# Schematic.net
KiCad netlist of a schematic drawn in Altium Designer
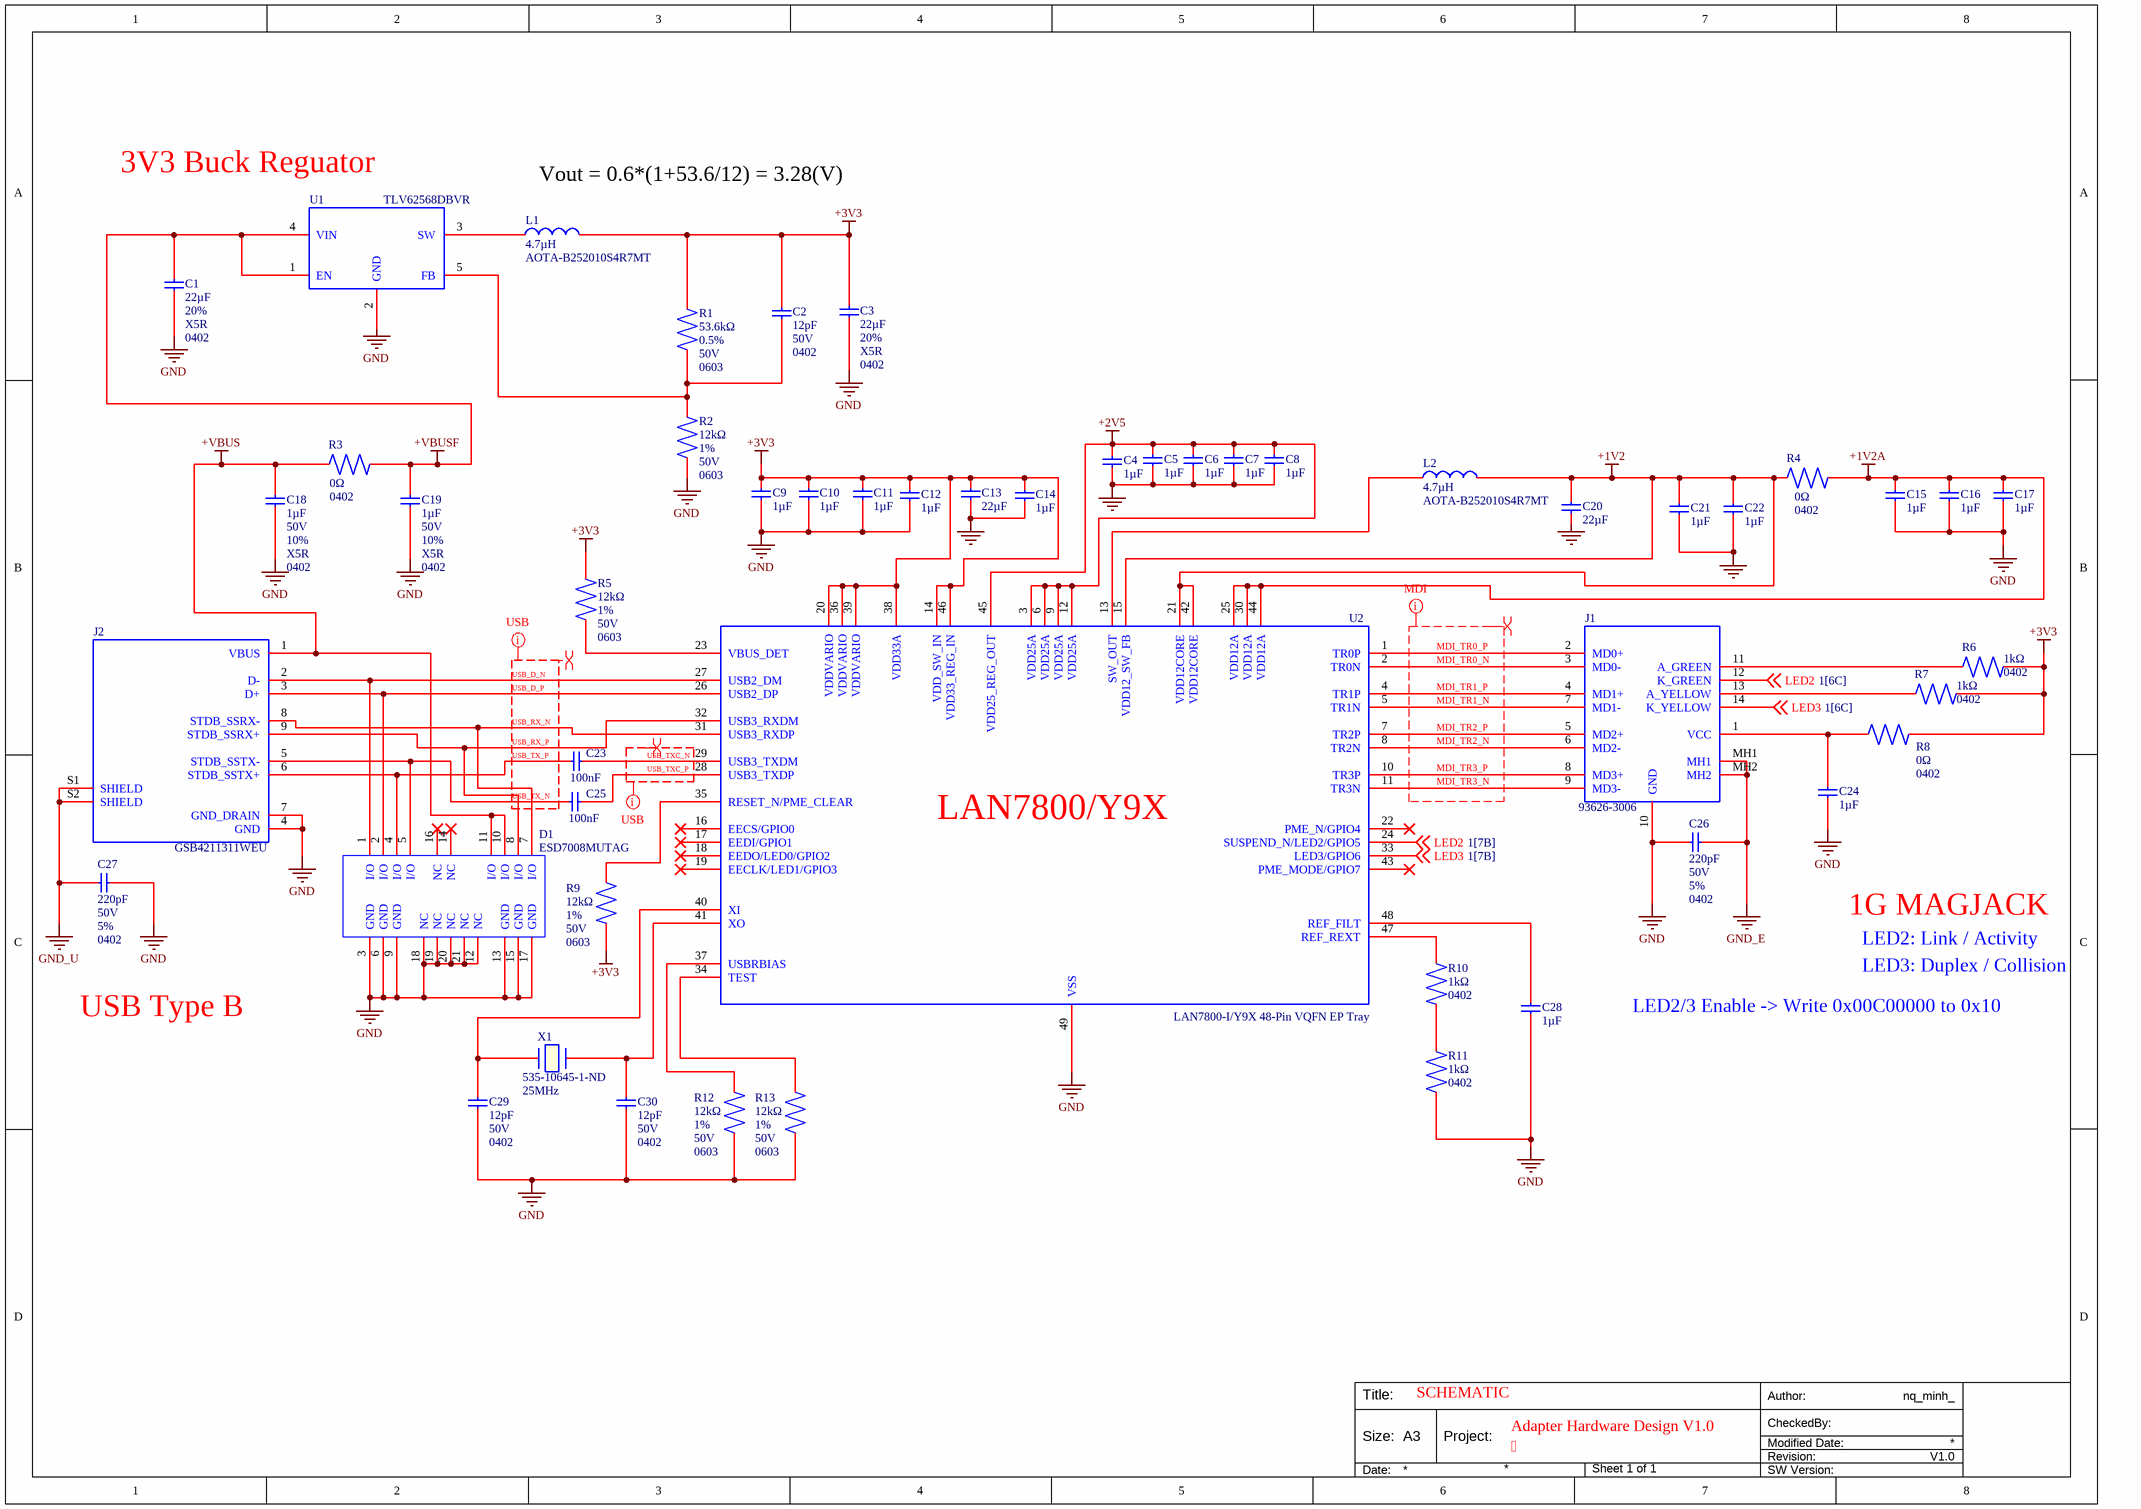
[diagram p0: Schematic.SchDoc]

(export (version "E")
  (design (tool "Eeschema 10.0.6"))
  (components
    (comp (ref "C1")
      (value "22µF")
      (footprint "C0402")
      (description "6.3V 22uF X5R ±20% 0402 Multilayer Ceramic Capacitors MLCC - SMD/SMT ROHS")
      (fields
        (field (name "MANUFACTURER") "Murata")
        (field (name "MANUFACTURER PART NUMBER") "GRM155R60J226ME11D")
        (field (name "TOLERANCE") "20%")
        (field (name "DIELECTRIC") "X5R")
        (field (name "CASE/PACKAGE") "0402")
      )
      (libsource (lib "Schlib") (part "C0402_MLCC_22uF_X5R_6.3V"))
    )
    (comp (ref "C2")
      (value "12pF")
      (footprint "C0402")
      (description "50V 12pF C0G ±1% 0402 Multilayer Ceramic Capacitors MLCC - SMD/SMT ROHS")
      (fields
        (field (name "MANUFACTURER") "Murata")
        (field (name "MANUFACTURER PART NUMBER") "GCM1555C1H120FA16D")
        (field (name "VOLTAGE RATING") "50V")
        (field (name "CASE/PACKAGE") "0402")
      )
      (libsource (lib "Schlib") (part "C0402_MLCC_12pF_c0G_50V"))
    )
    (comp (ref "C3")
      (value "22µF")
      (footprint "C0402")
      (description "6.3V 22uF X5R ±20% 0402 Multilayer Ceramic Capacitors MLCC - SMD/SMT ROHS")
      (fields
        (field (name "MANUFACTURER") "Murata")
        (field (name "MANUFACTURER PART NUMBER") "GRM155R60J226ME11D")
        (field (name "TOLERANCE") "20%")
        (field (name "DIELECTRIC") "X5R")
        (field (name "CASE/PACKAGE") "0402")
      )
      (libsource (lib "Schlib") (part "C0402_MLCC_22uF_X5R_6.3V"))
    )
    (comp (ref "C4")
      (value "1µF")
      (footprint "C0402")
      (description "Ceramic Capacitor, Multilayer, Ceramic, 50V, 10% +Tol, 10% -Tol, X5R, 1uF, Surface Mount, 0402")
      (fields
        (field (name "MANUFACTURER") "Murata")
        (field (name "MANUFACTURER PART NUMBER") "GRM155R61H105KE05D")
      )
      (libsource (lib "Schlib") (part "C0402_MLCC_1uF_X5R_50V"))
    )
    (comp (ref "C5")
      (value "1µF")
      (footprint "C0402")
      (description "Ceramic Capacitor, Multilayer, Ceramic, 50V, 10% +Tol, 10% -Tol, X5R, 1uF, Surface Mount, 0402")
      (fields
        (field (name "MANUFACTURER") "Murata")
        (field (name "MANUFACTURER PART NUMBER") "GRM155R61H105KE05D")
      )
      (libsource (lib "Schlib") (part "C0402_MLCC_1uF_X5R_50V"))
    )
    (comp (ref "C6")
      (value "1µF")
      (footprint "C0402")
      (description "Ceramic Capacitor, Multilayer, Ceramic, 50V, 10% +Tol, 10% -Tol, X5R, 1uF, Surface Mount, 0402")
      (fields
        (field (name "MANUFACTURER") "Murata")
        (field (name "MANUFACTURER PART NUMBER") "GRM155R61H105KE05D")
      )
      (libsource (lib "Schlib") (part "C0402_MLCC_1uF_X5R_50V"))
    )
    (comp (ref "C7")
      (value "1µF")
      (footprint "C0402")
      (description "Ceramic Capacitor, Multilayer, Ceramic, 50V, 10% +Tol, 10% -Tol, X5R, 1uF, Surface Mount, 0402")
      (fields
        (field (name "MANUFACTURER") "Murata")
        (field (name "MANUFACTURER PART NUMBER") "GRM155R61H105KE05D")
      )
      (libsource (lib "Schlib") (part "C0402_MLCC_1uF_X5R_50V"))
    )
    (comp (ref "C8")
      (value "1µF")
      (footprint "C0402")
      (description "Ceramic Capacitor, Multilayer, Ceramic, 50V, 10% +Tol, 10% -Tol, X5R, 1uF, Surface Mount, 0402")
      (fields
        (field (name "MANUFACTURER") "Murata")
        (field (name "MANUFACTURER PART NUMBER") "GRM155R61H105KE05D")
      )
      (libsource (lib "Schlib") (part "C0402_MLCC_1uF_X5R_50V"))
    )
    (comp (ref "C9")
      (value "1µF")
      (footprint "C0402")
      (description "Ceramic Capacitor, Multilayer, Ceramic, 50V, 10% +Tol, 10% -Tol, X5R, 1uF, Surface Mount, 0402")
      (fields
        (field (name "MANUFACTURER") "Murata")
        (field (name "MANUFACTURER PART NUMBER") "GRM155R61H105KE05D")
      )
      (libsource (lib "Schlib") (part "C0402_MLCC_1uF_X5R_50V"))
    )
    (comp (ref "C10")
      (value "1µF")
      (footprint "C0402")
      (description "Ceramic Capacitor, Multilayer, Ceramic, 50V, 10% +Tol, 10% -Tol, X5R, 1uF, Surface Mount, 0402")
      (fields
        (field (name "MANUFACTURER") "Murata")
        (field (name "MANUFACTURER PART NUMBER") "GRM155R61H105KE05D")
      )
      (libsource (lib "Schlib") (part "C0402_MLCC_1uF_X5R_50V"))
    )
    (comp (ref "C11")
      (value "1µF")
      (footprint "C0402")
      (description "Ceramic Capacitor, Multilayer, Ceramic, 50V, 10% +Tol, 10% -Tol, X5R, 1uF, Surface Mount, 0402")
      (fields
        (field (name "MANUFACTURER") "Murata")
        (field (name "MANUFACTURER PART NUMBER") "GRM155R61H105KE05D")
      )
      (libsource (lib "Schlib") (part "C0402_MLCC_1uF_X5R_50V"))
    )
    (comp (ref "C12")
      (value "1µF")
      (footprint "C0402")
      (description "Ceramic Capacitor, Multilayer, Ceramic, 50V, 10% +Tol, 10% -Tol, X5R, 1uF, Surface Mount, 0402")
      (fields
        (field (name "MANUFACTURER") "Murata")
        (field (name "MANUFACTURER PART NUMBER") "GRM155R61H105KE05D")
      )
      (libsource (lib "Schlib") (part "C0402_MLCC_1uF_X5R_50V"))
    )
    (comp (ref "C13")
      (value "22µF")
      (footprint "C0402")
      (description "6.3V 22uF X5R ±20% 0402 Multilayer Ceramic Capacitors MLCC - SMD/SMT ROHS")
      (fields
        (field (name "MANUFACTURER") "Murata")
        (field (name "MANUFACTURER PART NUMBER") "GRM155R60J226ME11D")
      )
      (libsource (lib "Schlib") (part "C0402_MLCC_22uF_X5R_6.3V"))
    )
    (comp (ref "C14")
      (value "1µF")
      (footprint "C0402")
      (description "Ceramic Capacitor, Multilayer, Ceramic, 50V, 10% +Tol, 10% -Tol, X5R, 1uF, Surface Mount, 0402")
      (fields
        (field (name "MANUFACTURER") "Murata")
        (field (name "MANUFACTURER PART NUMBER") "GRM155R61H105KE05D")
      )
      (libsource (lib "Schlib") (part "C0402_MLCC_1uF_X5R_50V"))
    )
    (comp (ref "C15")
      (value "1µF")
      (footprint "C0402")
      (description "Ceramic Capacitor, Multilayer, Ceramic, 50V, 10% +Tol, 10% -Tol, X5R, 1uF, Surface Mount, 0402")
      (fields
        (field (name "MANUFACTURER") "Murata")
        (field (name "MANUFACTURER PART NUMBER") "GRM155R61H105KE05D")
      )
      (libsource (lib "Schlib") (part "C0402_MLCC_1uF_X5R_50V"))
    )
    (comp (ref "C16")
      (value "1µF")
      (footprint "C0402")
      (description "Ceramic Capacitor, Multilayer, Ceramic, 50V, 10% +Tol, 10% -Tol, X5R, 1uF, Surface Mount, 0402")
      (fields
        (field (name "MANUFACTURER") "Murata")
        (field (name "MANUFACTURER PART NUMBER") "GRM155R61H105KE05D")
      )
      (libsource (lib "Schlib") (part "C0402_MLCC_1uF_X5R_50V"))
    )
    (comp (ref "C17")
      (value "1µF")
      (footprint "C0402")
      (description "Ceramic Capacitor, Multilayer, Ceramic, 50V, 10% +Tol, 10% -Tol, X5R, 1uF, Surface Mount, 0402")
      (fields
        (field (name "MANUFACTURER") "Murata")
        (field (name "MANUFACTURER PART NUMBER") "GRM155R61H105KE05D")
      )
      (libsource (lib "Schlib") (part "C0402_MLCC_1uF_X5R_50V"))
    )
    (comp (ref "C18")
      (value "1µF")
      (footprint "C0402")
      (description "Ceramic Capacitor, Multilayer, Ceramic, 50V, 10% +Tol, 10% -Tol, X5R, 1uF, Surface Mount, 0402")
      (fields
        (field (name "MANUFACTURER") "Murata")
        (field (name "MANUFACTURER PART NUMBER") "GRM155R61H105KE05D")
        (field (name "VOLTAGE RATING") "50V")
        (field (name "TOLERANCE") "10%")
        (field (name "DIELECTRIC") "X5R")
        (field (name "CASE/PACKAGE") "0402")
      )
      (libsource (lib "Schlib") (part "C0402_MLCC_1uF_X5R_50V"))
    )
    (comp (ref "C19")
      (value "1µF")
      (footprint "C0402")
      (description "Ceramic Capacitor, Multilayer, Ceramic, 50V, 10% +Tol, 10% -Tol, X5R, 1uF, Surface Mount, 0402")
      (fields
        (field (name "MANUFACTURER") "Murata")
        (field (name "MANUFACTURER PART NUMBER") "GRM155R61H105KE05D")
        (field (name "VOLTAGE RATING") "50V")
        (field (name "TOLERANCE") "10%")
        (field (name "DIELECTRIC") "X5R")
        (field (name "CASE/PACKAGE") "0402")
      )
      (libsource (lib "Schlib") (part "C0402_MLCC_1uF_X5R_50V"))
    )
    (comp (ref "C20")
      (value "22µF")
      (footprint "C0402")
      (description "6.3V 22uF X5R ±20% 0402 Multilayer Ceramic Capacitors MLCC - SMD/SMT ROHS")
      (fields
        (field (name "MANUFACTURER") "Murata")
        (field (name "MANUFACTURER PART NUMBER") "GRM155R60J226ME11D")
      )
      (libsource (lib "Schlib") (part "C0402_MLCC_22uF_X5R_6.3V"))
    )
    (comp (ref "C21")
      (value "1µF")
      (footprint "C0402")
      (description "Ceramic Capacitor, Multilayer, Ceramic, 50V, 10% +Tol, 10% -Tol, X5R, 1uF, Surface Mount, 0402")
      (fields
        (field (name "MANUFACTURER") "Murata")
        (field (name "MANUFACTURER PART NUMBER") "GRM155R61H105KE05D")
      )
      (libsource (lib "Schlib") (part "C0402_MLCC_1uF_X5R_50V"))
    )
    (comp (ref "C22")
      (value "1µF")
      (footprint "C0402")
      (description "Ceramic Capacitor, Multilayer, Ceramic, 50V, 10% +Tol, 10% -Tol, X5R, 1uF, Surface Mount, 0402")
      (fields
        (field (name "MANUFACTURER") "Murata")
        (field (name "MANUFACTURER PART NUMBER") "GRM155R61H105KE05D")
      )
      (libsource (lib "Schlib") (part "C0402_MLCC_1uF_X5R_50V"))
    )
    (comp (ref "C23")
      (value "100nF")
      (footprint "C0402")
      (description "50V 100nF X7R ±10% 0402 Multilayer Ceramic Capacitors MLCC - SMD/SMT ROHS")
      (fields
        (field (name "MANUFACTURER") "Yageo Group")
        (field (name "MANUFACTURER PART NUMBER") "CC0402KRX7R9BB104")
      )
      (libsource (lib "Schlib") (part "C0402_MLCC_100nF_X7R_50V"))
    )
    (comp (ref "C24")
      (value "1µF")
      (footprint "C0402")
      (description "Ceramic Capacitor, Multilayer, Ceramic, 50V, 10% +Tol, 10% -Tol, X5R, 1uF, Surface Mount, 0402")
      (fields
        (field (name "MANUFACTURER") "Murata")
        (field (name "MANUFACTURER PART NUMBER") "GRM155R61H105KE05D")
      )
      (libsource (lib "Schlib") (part "C0402_MLCC_1uF_X5R_50V"))
    )
    (comp (ref "C25")
      (value "100nF")
      (footprint "C0402")
      (description "50V 100nF X7R ±10% 0402 Multilayer Ceramic Capacitors MLCC - SMD/SMT ROHS")
      (fields
        (field (name "MANUFACTURER") "Yageo Group")
        (field (name "MANUFACTURER PART NUMBER") "CC0402KRX7R9BB104")
      )
      (libsource (lib "Schlib") (part "C0402_MLCC_100nF_X7R_50V"))
    )
    (comp (ref "C26")
      (value "220pF")
      (footprint "C0402")
      (description "50V 220pF C0G ±5% 0402 Multilayer Ceramic Capacitors MLCC - SMD/SMT ROHS")
      (fields
        (field (name "MANUFACTURER") "Murata")
        (field (name "MANUFACTURER PART NUMBER") "GRM1555C1H221JA01D")
        (field (name "VOLTAGE") "50V")
        (field (name "TOLERANCE") "5%")
        (field (name "CASE/PACKAGE") "0402")
      )
      (libsource (lib "Schlib") (part "C0402_MLCC_220pF_C0G_50V"))
    )
    (comp (ref "C27")
      (value "220pF")
      (footprint "C0402")
      (description "50V 220pF C0G ±5% 0402 Multilayer Ceramic Capacitors MLCC - SMD/SMT ROHS")
      (fields
        (field (name "MANUFACTURER") "Murata")
        (field (name "MANUFACTURER PART NUMBER") "GRM1555C1H221JA01D")
        (field (name "VOLTAGE") "50V")
        (field (name "TOLERANCE") "5%")
        (field (name "CASE/PACKAGE") "0402")
      )
      (libsource (lib "Schlib") (part "C0402_MLCC_220pF_C0G_50V"))
    )
    (comp (ref "C28")
      (value "1µF")
      (footprint "C0402")
      (description "Ceramic Capacitor, Multilayer, Ceramic, 50V, 10% +Tol, 10% -Tol, X5R, 1uF, Surface Mount, 0402")
      (fields
        (field (name "MANUFACTURER") "Murata")
        (field (name "MANUFACTURER PART NUMBER") "GRM155R61H105KE05D")
      )
      (libsource (lib "Schlib") (part "C0402_MLCC_1uF_X5R_50V"))
    )
    (comp (ref "C29")
      (value "12pF")
      (footprint "C0402")
      (description "50V 12pF C0G ±1% 0402 Multilayer Ceramic Capacitors MLCC - SMD/SMT ROHS")
      (fields
        (field (name "MANUFACTURER") "Murata")
        (field (name "MANUFACTURER PART NUMBER") "GCM1555C1H120FA16D")
        (field (name "VOLTAGE RATING") "50V")
        (field (name "CASE/PACKAGE") "0402")
      )
      (libsource (lib "Schlib") (part "C0402_MLCC_12pF_c0G_50V"))
    )
    (comp (ref "C30")
      (value "12pF")
      (footprint "C0402")
      (description "50V 12pF C0G ±1% 0402 Multilayer Ceramic Capacitors MLCC - SMD/SMT ROHS")
      (fields
        (field (name "MANUFACTURER") "Murata")
        (field (name "MANUFACTURER PART NUMBER") "GCM1555C1H120FA16D")
        (field (name "VOLTAGE RATING") "50V")
        (field (name "CASE/PACKAGE") "0402")
      )
      (libsource (lib "Schlib") (part "C0402_MLCC_12pF_c0G_50V"))
    )
    (comp (ref "D1")
      (value "ESD7008MUTAG")
      (footprint "ESD7008MUTAG")
      (description "ESD Suppressor Diode TVS Bi-Dir 5V 10Vc 18-Pin UDFN EP T/R")
      (fields (field (name "MANUFACTURER") "onsemi") (field (name "LCSC PART") "C260424"))
      (libsource (lib "Schlib") (part "ESD7008MUTAG"))
    )
    (comp (ref "J1")
      (value "93626-3006")
      (footprint "936263006")
      (description "Modular Connectors / Ethernet Connectors MXMag GIG 8CORE RJ45 W/ LEDs GRN/YLW RA")
      (fields (field (name "MANUFACTURER") "Molex") (field (name "LCSC PART") "C6377799"))
      (libsource (lib "Schlib") (part "93626-3006"))
    )
    (comp (ref "J2")
      (value "GSB4211311WEU")
      (footprint "AMPHENOL_GSB4211311WEU")
      (description "USB Connector, 4 Contact(s), Female, Right Angle, Solder Terminal, Receptacle")
      (fields (field (name "MANUFACTURER") "Amphenol") (field (name "LCSC PART") "C5429210"))
      (libsource (lib "Schlib") (part "GSB4211311WEU"))
    )
    (comp (ref "L1")
      (value "4.7µH")
      (footprint "INDC2520X100N")
      (description "Inductor Power Mini Molded/Shielded Wirewound 4.7uH 20% 1MHz 1.6A 0.136Ohm DCR 1008")
      (fields
        (field (name "MANUFACTURER") "Abracon")
        (field (name "TOLERANCE") "20%")
        (field (name "MANUFACTURER PART NUMBER") "AOTA-B252010S4R7MT")
      )
      (libsource (lib "Schlib") (part "AOTA-B252010S4R7MT"))
    )
    (comp (ref "L2")
      (value "4.7µH")
      (footprint "INDC2520X100N")
      (description "Inductor Power Mini Molded/Shielded Wirewound 4.7uH 20% 1MHz 1.6A 0.136Ohm DCR 1008")
      (fields
        (field (name "MANUFACTURER") "Abracon")
        (field (name "TOLERANCE") "20%")
        (field (name "MANUFACTURER PART NUMBER") "AOTA-B252010S4R7MT")
      )
      (libsource (lib "Schlib") (part "AOTA-B252010S4R7MT"))
    )
    (comp (ref "R1")
      (value "53.6kΩ")
      (footprint "RESC1608X55N")
      (description "Fixed Resistor, Thin Film, 0.1W, 53600ohm, 75V, 0.5% +/-Tol, 50ppm/Cel, Surface Mount, 0603")
      (fields
        (field (name "MANUFACTURER") "Yageo Group")
        (field (name "MANUFACTURER PART NUMBER") "RT0603DRE0753K6L")
        (field (name "TOLERANCE") "0.5%")
        (field (name "VOLTAGE RATING (DC)") "50V")
        (field (name "CASE/PACKAGE") "0603")
      )
      (libsource (lib "Schlib") (part "R0603_53.6kΩ_±0.5%"))
    )
    (comp (ref "R2")
      (value "12kΩ")
      (footprint "RC0603N_YAG-L")
      (description "100mW Thick Film Resistors 75V ±100ppm/℃ ±1% 12kΩ 0603 Chip Resistor - Surface Mount ROHS")
      (fields
        (field (name "MANUFACTURER") "Yageo Group")
        (field (name "MANUFACTURER PART NUMBER") "RC0603FR-0712KL")
        (field (name "TOLERANCE") "1%")
        (field (name "VOLTAGE RATING") "50V")
        (field (name "CASE/PACKAGE") "0603")
      )
      (libsource (lib "Schlib") (part "R0603_12kΩ_±1%"))
    )
    (comp (ref "R3")
      (value "0Ω")
      (footprint "RC0402N_YAG-L")
      (description "GENERAL PURPOSE CHIP RESISTOR Metal Glaze/thick Film, 0.0625W, 0ohm, Surface Mount, 0402")
      (fields
        (field (name "MANUFACTURER") "Yageo Group")
        (field (name "MANUFACTURER PART NUMBER") "RC0402JR-070RL")
        (field (name "CASE/PACKAGE") "0402")
      )
      (libsource (lib "Schlib") (part "RC0402JR-070RL"))
    )
    (comp (ref "R4")
      (value "0Ω")
      (footprint "RC0402N_YAG-L")
      (description "GENERAL PURPOSE CHIP RESISTOR Metal Glaze/thick Film, 0.0625W, 0ohm, Surface Mount, 0402")
      (fields
        (field (name "MANUFACTURER") "Yageo Group")
        (field (name "MANUFACTURER PART NUMBER") "RC0402JR-070RL")
        (field (name "CASE/PACKAGE") "0402")
      )
      (libsource (lib "Schlib") (part "RC0402JR-070RL"))
    )
    (comp (ref "R5")
      (value "12kΩ")
      (footprint "RC0603N_YAG-L")
      (description "100mW Thick Film Resistors 75V ±100ppm/℃ ±1% 12kΩ 0603 Chip Resistor - Surface Mount ROHS")
      (fields
        (field (name "MANUFACTURER") "Yageo Group")
        (field (name "MANUFACTURER PART NUMBER") "RC0603FR-0712KL")
        (field (name "TOLERANCE") "1%")
        (field (name "VOLTAGE RATING") "50V")
        (field (name "CASE/PACKAGE") "0603")
      )
      (libsource (lib "Schlib") (part "R0603_12kΩ_±1%"))
    )
    (comp (ref "R6")
      (value "1kΩ")
      (footprint "RC0402N_YAG-L")
      (fields
        (field (name "MANUFACTURER") "Yageo Group")
        (field (name "MANUFACTURER PART NUMBER") "RT0402BRD071KL")
        (field (name "LCSC PART") "C852624")
        (field (name "CASE/PACKAGE") "0402")
      )
      (libsource (lib "Schlib") (part "R0402_1kΩ_0.1%"))
    )
    (comp (ref "R7")
      (value "1kΩ")
      (footprint "RC0402N_YAG-L")
      (fields
        (field (name "MANUFACTURER") "Yageo Group")
        (field (name "MANUFACTURER PART NUMBER") "RT0402BRD071KL")
        (field (name "LCSC PART") "C852624")
        (field (name "CASE/PACKAGE") "0402")
      )
      (libsource (lib "Schlib") (part "R0402_1kΩ_0.1%"))
    )
    (comp (ref "R8")
      (value "0Ω")
      (footprint "RC0402N_YAG-L")
      (description "GENERAL PURPOSE CHIP RESISTOR Metal Glaze/thick Film, 0.0625W, 0ohm, Surface Mount, 0402")
      (fields
        (field (name "MANUFACTURER") "Yageo Group")
        (field (name "MANUFACTURER PART NUMBER") "RC0402JR-070RL")
        (field (name "CASE/PACKAGE") "0402")
      )
      (libsource (lib "Schlib") (part "RC0402JR-070RL"))
    )
    (comp (ref "R9")
      (value "12kΩ")
      (footprint "RC0603N_YAG-L")
      (description "100mW Thick Film Resistors 75V ±100ppm/℃ ±1% 12kΩ 0603 Chip Resistor - Surface Mount ROHS")
      (fields
        (field (name "MANUFACTURER") "Yageo Group")
        (field (name "MANUFACTURER PART NUMBER") "RC0603FR-0712KL")
        (field (name "TOLERANCE") "1%")
        (field (name "VOLTAGE RATING") "50V")
        (field (name "CASE/PACKAGE") "0603")
      )
      (libsource (lib "Schlib") (part "R0603_12kΩ_±1%"))
    )
    (comp (ref "R10")
      (value "1kΩ")
      (footprint "RC0402N_YAG-L")
      (fields
        (field (name "MANUFACTURER") "Yageo Group")
        (field (name "MANUFACTURER PART NUMBER") "RT0402BRD071KL")
        (field (name "LCSC PART") "C852624")
        (field (name "CASE/PACKAGE") "0402")
      )
      (libsource (lib "Schlib") (part "R0402_1kΩ_0.1%"))
    )
    (comp (ref "R11")
      (value "1kΩ")
      (footprint "RC0402N_YAG-L")
      (fields
        (field (name "MANUFACTURER") "Yageo Group")
        (field (name "MANUFACTURER PART NUMBER") "RT0402BRD071KL")
        (field (name "LCSC PART") "C852624")
        (field (name "CASE/PACKAGE") "0402")
      )
      (libsource (lib "Schlib") (part "R0402_1kΩ_0.1%"))
    )
    (comp (ref "R12")
      (value "12kΩ")
      (footprint "RC0603N_YAG-L")
      (description "100mW Thick Film Resistors 75V ±100ppm/℃ ±1% 12kΩ 0603 Chip Resistor - Surface Mount ROHS")
      (fields
        (field (name "MANUFACTURER") "Yageo Group")
        (field (name "MANUFACTURER PART NUMBER") "RC0603FR-0712KL")
        (field (name "TOLERANCE") "1%")
        (field (name "VOLTAGE RATING") "50V")
        (field (name "CASE/PACKAGE") "0603")
      )
      (libsource (lib "Schlib") (part "R0603_12kΩ_±1%"))
    )
    (comp (ref "R13")
      (value "12kΩ")
      (footprint "RC0603N_YAG-L")
      (description "100mW Thick Film Resistors 75V ±100ppm/℃ ±1% 12kΩ 0603 Chip Resistor - Surface Mount ROHS")
      (fields
        (field (name "MANUFACTURER") "Yageo Group")
        (field (name "MANUFACTURER PART NUMBER") "RC0603FR-0712KL")
        (field (name "TOLERANCE") "1%")
        (field (name "VOLTAGE RATING") "50V")
        (field (name "CASE/PACKAGE") "0603")
      )
      (libsource (lib "Schlib") (part "R0603_12kΩ_±1%"))
    )
    (comp (ref "U1")
      (value "TLV62568DBVR")
      (footprint "SOT95P280X145-5N")
      (description "ROHS3Compliant Adjustable Positive DUAL Switching Regulator IC -40C~125C TJ 1.5MHz 1A 1.6mm")
      (fields (field (name "MANUFACTURER") "Texas Instruments") (field (name "LCSC PART") "C163219"))
      (libsource (lib "Schlib") (part "TLV62568DBVR"))
    )
    (comp (ref "U2")
      (value "LAN7800-I/Y9X 48-Pin VQFN EP Tray")
      (footprint "SQFN48_7X7_Y9X_MCH-L")
      (description "Ethernet CTLR Single Chip 10Mbps/100Mbps/1000Mbps 1.8V/3.3V Automotive 48-Pin VQFN EP Tray")
      (fields
        (field (name "MANUFACTURER") "Microchip")
        (field (name "MANUFACTURER PART NUMBER") "LAN7800-I/Y9X")
      )
      (libsource (lib "Schlib") (part "LAN7800-I/Y9X"))
    )
    (comp (ref "X1")
      (value "ABM3-25.000MHZ-D2Y-T 25Mhz")
      (footprint "XTAL_ABM3_ABR-L")
      (description "Crystal 25MHz ±20ppm (Tol) ±30ppm (Stability) 18pF FUND 30Ohm 2-Pin Mini-CSMD T/R")
      (fields
        (field (name "SUPPLIER PART NUMBER") "535-10645-1-ND")
        (field (name "MANUFACTURER") "Abracon")
        (field (name "MANUFACTURER PART NUMBER") "ABM3-25.000MHZ-D2Y-T")
        (field (name "FREQUENCY") "25MHz")
      )
      (libsource (lib "Schlib") (part "ABM3-25.000MHZ-D2Y-T"))
    )
  )
  (nets
    (net (code "1") (name "+1V2") (class "Default")
      (node (ref "C20") (pin "2") (pinfunction "2_2") (pintype "passive"))
      (node (ref "C21") (pin "1") (pinfunction "1_1") (pintype "passive"))
      (node (ref "C22") (pin "1") (pinfunction "1_1") (pintype "passive"))
      (node (ref "L2") (pin "2") (pinfunction "2_2") (pintype "passive"))
      (node (ref "R4") (pin "1") (pinfunction "1_1") (pintype "passive"))
      (node (ref "U2") (pin "15") (pinfunction "VDD12_SW_FB_15") (pintype "passive"))
      (node (ref "U2") (pin "21") (pinfunction "VDD12CORE_21") (pintype "passive"))
      (node (ref "U2") (pin "42") (pinfunction "VDD12CORE_42") (pintype "passive"))
    )
    (net (code "2") (name "+1V2A") (class "Default")
      (node (ref "C15") (pin "1") (pinfunction "1_1") (pintype "passive"))
      (node (ref "C16") (pin "1") (pinfunction "1_1") (pintype "passive"))
      (node (ref "C17") (pin "1") (pinfunction "1_1") (pintype "passive"))
      (node (ref "R4") (pin "2") (pinfunction "2_2") (pintype "passive"))
      (node (ref "U2") (pin "25") (pinfunction "VDD12A_25") (pintype "passive"))
      (node (ref "U2") (pin "30") (pinfunction "VDD12A_30") (pintype "passive"))
      (node (ref "U2") (pin "44") (pinfunction "VDD12A_44") (pintype "passive"))
    )
    (net (code "3") (name "+2V5") (class "Default")
      (node (ref "C4") (pin "1") (pinfunction "1_1") (pintype "passive"))
      (node (ref "C5") (pin "2") (pinfunction "2_2") (pintype "passive"))
      (node (ref "C6") (pin "2") (pinfunction "2_2") (pintype "passive"))
      (node (ref "C7") (pin "2") (pinfunction "2_2") (pintype "passive"))
      (node (ref "C8") (pin "2") (pinfunction "2_2") (pintype "passive"))
      (node (ref "U2") (pin "12") (pinfunction "VDD25A_12") (pintype "passive"))
      (node (ref "U2") (pin "3") (pinfunction "VDD25A_3") (pintype "passive"))
      (node (ref "U2") (pin "45") (pinfunction "VDD25_REG_OUT_45") (pintype "passive"))
      (node (ref "U2") (pin "6") (pinfunction "VDD25A_6") (pintype "passive"))
      (node (ref "U2") (pin "9") (pinfunction "VDD25A_9") (pintype "passive"))
    )
    (net (code "4") (name "+3V3") (class "Default")
      (node (ref "C10") (pin "1") (pinfunction "1_1") (pintype "passive"))
      (node (ref "C11") (pin "1") (pinfunction "1_1") (pintype "passive"))
      (node (ref "C12") (pin "1") (pinfunction "1_1") (pintype "passive"))
      (node (ref "C13") (pin "2") (pinfunction "2_2") (pintype "passive"))
      (node (ref "C14") (pin "1") (pinfunction "1_1") (pintype "passive"))
      (node (ref "C2") (pin "2") (pinfunction "2_2") (pintype "passive"))
      (node (ref "C3") (pin "2") (pinfunction "2_2") (pintype "passive"))
      (node (ref "C9") (pin "1") (pinfunction "1_1") (pintype "passive"))
      (node (ref "L1") (pin "2") (pinfunction "2_2") (pintype "passive"))
      (node (ref "R1") (pin "2") (pinfunction "2_2") (pintype "passive"))
      (node (ref "R5") (pin "2") (pinfunction "2_2") (pintype "passive"))
      (node (ref "R6") (pin "2") (pinfunction "2_2") (pintype "passive"))
      (node (ref "R7") (pin "2") (pinfunction "2_2") (pintype "passive"))
      (node (ref "R8") (pin "2") (pinfunction "2_2") (pintype "passive"))
      (node (ref "R9") (pin "2") (pinfunction "2_2") (pintype "passive"))
      (node (ref "U2") (pin "14") (pinfunction "VDD_SW_IN_14") (pintype "passive"))
      (node (ref "U2") (pin "20") (pinfunction "VDDVARIO_20") (pintype "passive"))
      (node (ref "U2") (pin "36") (pinfunction "VDDVARIO_36") (pintype "passive"))
      (node (ref "U2") (pin "38") (pinfunction "VDD33A_38") (pintype "passive"))
      (node (ref "U2") (pin "39") (pinfunction "VDDVARIO_39") (pintype "passive"))
      (node (ref "U2") (pin "46") (pinfunction "VDD33_REG_IN_46") (pintype "passive"))
    )
    (net (code "5") (name "+VBUS") (class "Default")
      (node (ref "C18") (pin "2") (pinfunction "2_2") (pintype "passive"))
      (node (ref "D1") (pin "10") (pinfunction "I/O_10") (pintype "passive"))
      (node (ref "D1") (pin "11") (pinfunction "I/O_11") (pintype "passive"))
      (node (ref "J2") (pin "1") (pinfunction "VBUS_1") (pintype "passive"))
      (node (ref "R3") (pin "1") (pinfunction "1_1") (pintype "passive"))
    )
    (net (code "6") (name "+VBUSF") (class "Default")
      (node (ref "C1") (pin "2") (pinfunction "2_2") (pintype "passive"))
      (node (ref "C19") (pin "2") (pinfunction "2_2") (pintype "passive"))
      (node (ref "R3") (pin "2") (pinfunction "2_2") (pintype "passive"))
      (node (ref "U1") (pin "1") (pinfunction "EN_1") (pintype "passive"))
      (node (ref "U1") (pin "4") (pinfunction "VIN_4") (pintype "passive"))
    )
    (net (code "7") (name "/MDI_TR0_N") (class "Default")
      (node (ref "J1") (pin "3") (pinfunction "MD0-_3") (pintype "passive"))
      (node (ref "U2") (pin "2") (pinfunction "TR0N_2") (pintype "passive"))
    )
    (net (code "8") (name "/MDI_TR0_P") (class "Default")
      (node (ref "J1") (pin "2") (pinfunction "MD0+_2") (pintype "passive"))
      (node (ref "U2") (pin "1") (pinfunction "TR0P_1") (pintype "passive"))
    )
    (net (code "9") (name "/MDI_TR1_N") (class "Default")
      (node (ref "J1") (pin "7") (pinfunction "MD1-_7") (pintype "passive"))
      (node (ref "U2") (pin "5") (pinfunction "TR1N_5") (pintype "passive"))
    )
    (net (code "10") (name "/MDI_TR1_P") (class "Default")
      (node (ref "J1") (pin "4") (pinfunction "MD1+_4") (pintype "passive"))
      (node (ref "U2") (pin "4") (pinfunction "TR1P_4") (pintype "passive"))
    )
    (net (code "11") (name "/MDI_TR2_N") (class "Default")
      (node (ref "J1") (pin "6") (pinfunction "MD2-_6") (pintype "passive"))
      (node (ref "U2") (pin "8") (pinfunction "TR2N_8") (pintype "passive"))
    )
    (net (code "12") (name "/MDI_TR2_P") (class "Default")
      (node (ref "J1") (pin "5") (pinfunction "MD2+_5") (pintype "passive"))
      (node (ref "U2") (pin "7") (pinfunction "TR2P_7") (pintype "passive"))
    )
    (net (code "13") (name "/MDI_TR3_N") (class "Default")
      (node (ref "J1") (pin "9") (pinfunction "MD3-_9") (pintype "passive"))
      (node (ref "U2") (pin "11") (pinfunction "TR3N_11") (pintype "passive"))
    )
    (net (code "14") (name "/MDI_TR3_P") (class "Default")
      (node (ref "J1") (pin "8") (pinfunction "MD3+_8") (pintype "passive"))
      (node (ref "U2") (pin "10") (pinfunction "TR3P_10") (pintype "passive"))
    )
    (net (code "15") (name "/USB_D_N") (class "Default")
      (node (ref "D1") (pin "1") (pinfunction "I/O_1") (pintype "passive"))
      (node (ref "J2") (pin "2") (pinfunction "D-_2") (pintype "passive"))
      (node (ref "U2") (pin "27") (pinfunction "USB2_DM_27") (pintype "passive"))
    )
    (net (code "16") (name "/USB_D_P") (class "Default")
      (node (ref "D1") (pin "2") (pinfunction "I/O_2") (pintype "passive"))
      (node (ref "J2") (pin "3") (pinfunction "D+_3") (pintype "passive"))
      (node (ref "U2") (pin "26") (pinfunction "USB2_DP_26") (pintype "passive"))
    )
    (net (code "17") (name "/USB_RX_N") (class "Default")
      (node (ref "D1") (pin "7") (pinfunction "I/O_7") (pintype "passive"))
      (node (ref "J2") (pin "8") (pinfunction "STDB_SSRX-_8") (pintype "passive"))
      (node (ref "U2") (pin "31") (pinfunction "USB3_RXDP_31") (pintype "passive"))
    )
    (net (code "18") (name "/USB_RX_P") (class "Default")
      (node (ref "D1") (pin "8") (pinfunction "I/O_8") (pintype "passive"))
      (node (ref "J2") (pin "9") (pinfunction "STDB_SSRX+_9") (pintype "passive"))
      (node (ref "U2") (pin "32") (pinfunction "USB3_RXDM_32") (pintype "passive"))
    )
    (net (code "19") (name "/USB_TXC_N") (class "Default")
      (node (ref "C23") (pin "2") (pinfunction "2_2") (pintype "passive"))
      (node (ref "U2") (pin "29") (pinfunction "USB3_TXDM_29") (pintype "passive"))
    )
    (net (code "20") (name "/USB_TXC_P") (class "Default")
      (node (ref "C25") (pin "2") (pinfunction "2_2") (pintype "passive"))
      (node (ref "U2") (pin "28") (pinfunction "USB3_TXDP_28") (pintype "passive"))
    )
    (net (code "21") (name "/USB_TX_N") (class "Default")
      (node (ref "C25") (pin "1") (pinfunction "1_1") (pintype "passive"))
      (node (ref "D1") (pin "5") (pinfunction "I/O_5") (pintype "passive"))
      (node (ref "J2") (pin "5") (pinfunction "STDB_SSTX-_5") (pintype "passive"))
    )
    (net (code "22") (name "/USB_TX_P") (class "Default")
      (node (ref "C23") (pin "1") (pinfunction "1_1") (pintype "passive"))
      (node (ref "D1") (pin "4") (pinfunction "I/O_4") (pintype "passive"))
      (node (ref "J2") (pin "6") (pinfunction "STDB_SSTX+_6") (pintype "passive"))
    )
    (net (code "23") (name "GND") (class "Default")
      (node (ref "C1") (pin "1") (pinfunction "1_1") (pintype "passive"))
      (node (ref "C10") (pin "2") (pinfunction "2_2") (pintype "passive"))
      (node (ref "C11") (pin "2") (pinfunction "2_2") (pintype "passive"))
      (node (ref "C12") (pin "2") (pinfunction "2_2") (pintype "passive"))
      (node (ref "C13") (pin "1") (pinfunction "1_1") (pintype "passive"))
      (node (ref "C14") (pin "2") (pinfunction "2_2") (pintype "passive"))
      (node (ref "C15") (pin "2") (pinfunction "2_2") (pintype "passive"))
      (node (ref "C16") (pin "2") (pinfunction "2_2") (pintype "passive"))
      (node (ref "C17") (pin "2") (pinfunction "2_2") (pintype "passive"))
      (node (ref "C18") (pin "1") (pinfunction "1_1") (pintype "passive"))
      (node (ref "C19") (pin "1") (pinfunction "1_1") (pintype "passive"))
      (node (ref "C20") (pin "1") (pinfunction "1_1") (pintype "passive"))
      (node (ref "C21") (pin "2") (pinfunction "2_2") (pintype "passive"))
      (node (ref "C22") (pin "2") (pinfunction "2_2") (pintype "passive"))
      (node (ref "C24") (pin "2") (pinfunction "2_2") (pintype "passive"))
      (node (ref "C26") (pin "1") (pinfunction "1_1") (pintype "passive"))
      (node (ref "C27") (pin "1") (pinfunction "1_1") (pintype "passive"))
      (node (ref "C28") (pin "2") (pinfunction "2_2") (pintype "passive"))
      (node (ref "C29") (pin "1") (pinfunction "1_1") (pintype "passive"))
      (node (ref "C3") (pin "1") (pinfunction "1_1") (pintype "passive"))
      (node (ref "C30") (pin "1") (pinfunction "1_1") (pintype "passive"))
      (node (ref "C4") (pin "2") (pinfunction "2_2") (pintype "passive"))
      (node (ref "C5") (pin "1") (pinfunction "1_1") (pintype "passive"))
      (node (ref "C6") (pin "1") (pinfunction "1_1") (pintype "passive"))
      (node (ref "C7") (pin "1") (pinfunction "1_1") (pintype "passive"))
      (node (ref "C8") (pin "1") (pinfunction "1_1") (pintype "passive"))
      (node (ref "C9") (pin "2") (pinfunction "2_2") (pintype "passive"))
      (node (ref "D1") (pin "12") (pinfunction "NC_12") (pintype "passive"))
      (node (ref "D1") (pin "13") (pinfunction "GND_13") (pintype "passive"))
      (node (ref "D1") (pin "15") (pinfunction "GND_15") (pintype "passive"))
      (node (ref "D1") (pin "17") (pinfunction "GND_17") (pintype "passive"))
      (node (ref "D1") (pin "18") (pinfunction "NC_18") (pintype "passive"))
      (node (ref "D1") (pin "19") (pinfunction "NC_19") (pintype "passive"))
      (node (ref "D1") (pin "20") (pinfunction "NC_20") (pintype "passive"))
      (node (ref "D1") (pin "21") (pinfunction "NC_21") (pintype "passive"))
      (node (ref "D1") (pin "3") (pinfunction "GND_3") (pintype "passive"))
      (node (ref "D1") (pin "6") (pinfunction "GND_6") (pintype "passive"))
      (node (ref "D1") (pin "9") (pinfunction "GND_9") (pintype "passive"))
      (node (ref "J1") (pin "10") (pinfunction "GND_10") (pintype "passive"))
      (node (ref "J2") (pin "4") (pinfunction "GND_4") (pintype "passive"))
      (node (ref "J2") (pin "7") (pinfunction "GND_DRAIN_7") (pintype "passive"))
      (node (ref "R11") (pin "1") (pinfunction "1_1") (pintype "passive"))
      (node (ref "R12") (pin "2") (pinfunction "2_2") (pintype "passive"))
      (node (ref "R13") (pin "2") (pinfunction "2_2") (pintype "passive"))
      (node (ref "R2") (pin "1") (pinfunction "1_1") (pintype "passive"))
      (node (ref "U1") (pin "2") (pinfunction "GND_2") (pintype "passive"))
      (node (ref "U2") (pin "49") (pinfunction "VSS_49") (pintype "passive"))
    )
    (net (code "24") (name "GND_E") (class "Default")
      (node (ref "C26") (pin "2") (pinfunction "2_2") (pintype "passive"))
      (node (ref "J1") (pin "MH1") (pinfunction "MH1_MH1") (pintype "passive"))
      (node (ref "J1") (pin "MH2") (pinfunction "MH2_MH2") (pintype "passive"))
    )
    (net (code "25") (name "GND_U") (class "Default")
      (node (ref "C27") (pin "2") (pinfunction "2_2") (pintype "passive"))
      (node (ref "J2") (pin "S1") (pinfunction "SHIELD_S1") (pintype "passive"))
      (node (ref "J2") (pin "S2") (pinfunction "SHIELD_S2") (pintype "passive"))
    )
    (net (code "26") (name "LED2") (class "Default")
      (node (ref "J1") (pin "12") (pinfunction "K_GREEN_12") (pintype "passive"))
      (node (ref "U2") (pin "24") (pinfunction "SUSPEND_N/LED2/GPIO5_24") (pintype "passive"))
    )
    (net (code "27") (name "LED3") (class "Default")
      (node (ref "J1") (pin "14") (pinfunction "K_YELLOW_14") (pintype "passive"))
      (node (ref "U2") (pin "33") (pinfunction "LED3/GPIO6_33") (pintype "passive"))
    )
    (net (code "28") (name "Net-(J1-A_GREEN)") (class "Default")
      (node (ref "J1") (pin "11") (pinfunction "A_GREEN_11") (pintype "passive"))
      (node (ref "R6") (pin "1") (pinfunction "1_1") (pintype "passive"))
    )
    (net (code "29") (name "Net-(J1-A_YELLOW)") (class "Default")
      (node (ref "J1") (pin "13") (pinfunction "A_YELLOW_13") (pintype "passive"))
      (node (ref "R7") (pin "1") (pinfunction "1_1") (pintype "passive"))
    )
    (net (code "30") (name "Net-(J1-VCC)") (class "Default")
      (node (ref "C24") (pin "1") (pinfunction "1_1") (pintype "passive"))
      (node (ref "J1") (pin "1") (pinfunction "VCC_1") (pintype "passive"))
      (node (ref "R8") (pin "1") (pinfunction "1_1") (pintype "passive"))
    )
    (net (code "31") (name "Net-(R10-Pad1)") (class "Default")
      (node (ref "R10") (pin "1") (pinfunction "1_1") (pintype "passive"))
      (node (ref "R11") (pin "2") (pinfunction "2_2") (pintype "passive"))
    )
    (net (code "32") (name "Net-(U1-FB)") (class "Default")
      (node (ref "C2") (pin "1") (pinfunction "1_1") (pintype "passive"))
      (node (ref "R1") (pin "1") (pinfunction "1_1") (pintype "passive"))
      (node (ref "R2") (pin "2") (pinfunction "2_2") (pintype "passive"))
      (node (ref "U1") (pin "5") (pinfunction "FB_5") (pintype "passive"))
    )
    (net (code "33") (name "Net-(U1-SW)") (class "Default")
      (node (ref "L1") (pin "1") (pinfunction "1_1") (pintype "passive"))
      (node (ref "U1") (pin "3") (pinfunction "SW_3") (pintype "passive"))
    )
    (net (code "34") (name "Net-(U2-REF_FILT)") (class "Default")
      (node (ref "C28") (pin "1") (pinfunction "1_1") (pintype "passive"))
      (node (ref "U2") (pin "48") (pinfunction "REF_FILT_48") (pintype "passive"))
    )
    (net (code "35") (name "Net-(U2-REF_REXT)") (class "Default")
      (node (ref "R10") (pin "2") (pinfunction "2_2") (pintype "passive"))
      (node (ref "U2") (pin "47") (pinfunction "REF_REXT_47") (pintype "passive"))
    )
    (net (code "36") (name "Net-(U2-RESET_N{slash}PME_CLEAR)") (class "Default")
      (node (ref "R9") (pin "1") (pinfunction "1_1") (pintype "passive"))
      (node (ref "U2") (pin "35") (pinfunction "RESET_N/PME_CLEAR_35") (pintype "passive"))
    )
    (net (code "37") (name "Net-(U2-SW_OUT)") (class "Default")
      (node (ref "L2") (pin "1") (pinfunction "1_1") (pintype "passive"))
      (node (ref "U2") (pin "13") (pinfunction "SW_OUT_13") (pintype "passive"))
    )
    (net (code "38") (name "Net-(U2-TEST)") (class "Default")
      (node (ref "R13") (pin "1") (pinfunction "1_1") (pintype "passive"))
      (node (ref "U2") (pin "34") (pinfunction "TEST_34") (pintype "passive"))
    )
    (net (code "39") (name "Net-(U2-USBRBIAS)") (class "Default")
      (node (ref "R12") (pin "1") (pinfunction "1_1") (pintype "passive"))
      (node (ref "U2") (pin "37") (pinfunction "USBRBIAS_37") (pintype "passive"))
    )
    (net (code "40") (name "Net-(U2-VBUS_DET)") (class "Default")
      (node (ref "R5") (pin "1") (pinfunction "1_1") (pintype "passive"))
      (node (ref "U2") (pin "23") (pinfunction "VBUS_DET_23") (pintype "passive"))
    )
    (net (code "41") (name "Net-(U2-XI)") (class "Default")
      (node (ref "C29") (pin "2") (pinfunction "2_2") (pintype "passive"))
      (node (ref "U2") (pin "40") (pinfunction "XI_40") (pintype "passive"))
      (node (ref "X1") (pin "1") (pinfunction "1_1") (pintype "passive"))
    )
    (net (code "42") (name "Net-(U2-XO)") (class "Default")
      (node (ref "C30") (pin "2") (pinfunction "2_2") (pintype "passive"))
      (node (ref "U2") (pin "41") (pinfunction "XO_41") (pintype "passive"))
      (node (ref "X1") (pin "2") (pinfunction "2_2") (pintype "passive"))
    )
    (net (code "43") (name "unconnected-(D1-NC-Pad14)") (class "Default")
      (node (ref "D1") (pin "14") (pinfunction "NC_14") (pintype "passive+no_connect"))
    )
    (net (code "44") (name "unconnected-(D1-NC-Pad16)") (class "Default")
      (node (ref "D1") (pin "16") (pinfunction "NC_16") (pintype "passive+no_connect"))
    )
    (net (code "45") (name "unconnected-(U2-EECLK{slash}LED1{slash}GPIO3-Pad19)") (class "Default")
      (node (ref "U2") (pin "19") (pinfunction "EECLK/LED1/GPIO3_19") (pintype "passive+no_connect"))
    )
    (net (code "46") (name "unconnected-(U2-EECS{slash}GPIO0-Pad16)") (class "Default")
      (node (ref "U2") (pin "16") (pinfunction "EECS/GPIO0_16") (pintype "passive+no_connect"))
    )
    (net (code "47") (name "unconnected-(U2-EEDI{slash}GPIO1-Pad17)") (class "Default")
      (node (ref "U2") (pin "17") (pinfunction "EEDI/GPIO1_17") (pintype "passive+no_connect"))
    )
    (net (code "48") (name "unconnected-(U2-EEDO{slash}LED0{slash}GPIO2-Pad18)") (class "Default")
      (node (ref "U2") (pin "18") (pinfunction "EEDO/LED0/GPIO2_18") (pintype "passive+no_connect"))
    )
    (net (code "49") (name "unconnected-(U2-PME_MODE{slash}GPIO7-Pad43)") (class "Default")
      (node (ref "U2") (pin "43") (pinfunction "PME_MODE/GPIO7_43") (pintype "passive+no_connect"))
    )
    (net (code "50") (name "unconnected-(U2-PME_N{slash}GPIO4-Pad22)") (class "Default")
      (node (ref "U2") (pin "22") (pinfunction "PME_N/GPIO4_22") (pintype "passive+no_connect"))
    )
  )
)
